# Schema.net
KiCad netlist of a schematic drawn in Altium Designer
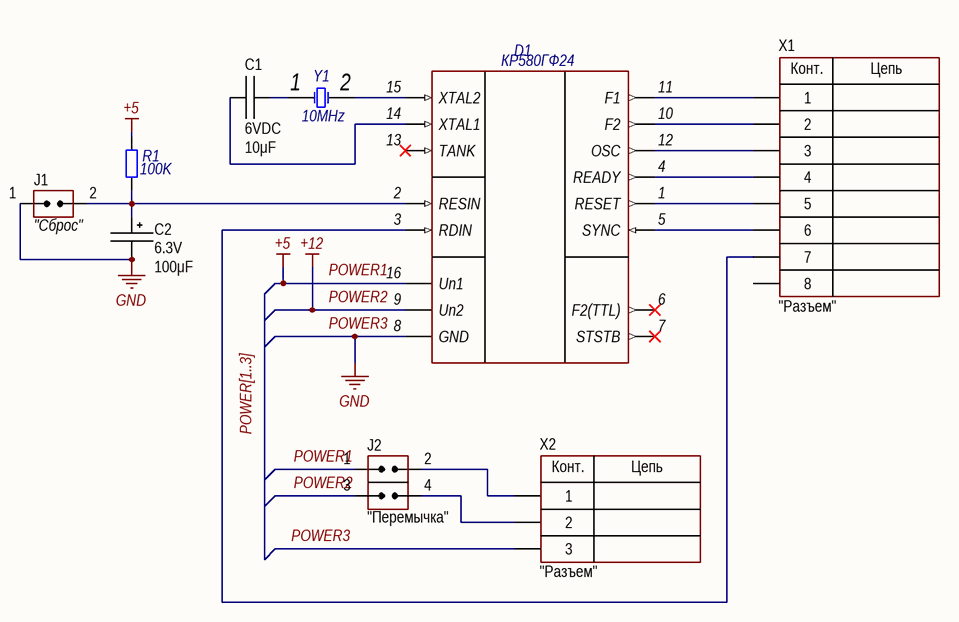
[diagram p0: Schema.SchDoc]

(export (version "E")
  (design (tool "Eeschema 10.0.6"))
  (components
    (comp (ref "C1")
      (value "10μF")
      (footprint "CustomCase:CAP: VY2")
      (fields
        (field (name "MANUFACTURER") "Epcos")
        (field (name "PARTNUMBER") "B32774D4106K000")
        (field (name "VALUEMANUFACTURERPARTNUMBER") "Film capacitor, 10μF, 6VDC, ±10%, 10.9mOhm, 31.5x15 mm, -40...+105°C")
        (field (name "VOLTAGE") "6VDC")
      )
      (libsource (lib "Capacitor") (part "Film"))
    )
    (comp (ref "C2")
      (value "100μF")
      (footprint "StandardCase:CAP: TANTAL-A")
      (fields
        (field (name "MANUFACTURER") "AVX")
        (field (name "PARTNUMBER") "F930J107KAAAJ6")
        (field (name "VALUEMANUFACTURERPARTNUMBER") "Tantalum capacitor, 100μF, 6.3V, ±10%, 2Ohm, case A (3216), -55...+125°C")
        (field (name "VOLTAGE") "6.3V")
      )
      (libsource (lib "Capacitor") (part "Tantal_A"))
    )
    (comp (ref "D1")
      (value "КР580ГФ24")
      (footprint "DIP16")
      (description "Генератор тактовых сигналов")
      (libsource (lib "IC.USSA") (part "КР580ГФ24"))
    )
    (comp (ref "J1")
      (value "~")
      (footprint "CustomCase:CON: PLS-2")
      (fields (field (name "COMMENTTEXT") "\"Сброс\""))
      (libsource (lib "Connector") (part "Jumper_single"))
    )
    (comp (ref "J2")
      (value "~")
      (footprint "CustomCase:CON: PLD-4")
      (fields (field (name "COMMENTTEXT") "\"Перемычка\""))
      (libsource (lib "Connector") (part "Jumper_double"))
    )
    (comp (ref "R1")
      (value "100K")
      (footprint "AXIAL-0.4")
      (description "Resistor")
      (fields (field (name "Comment") "Res2") (field (name "PUBLISHER") "Altium Limited"))
      (libsource (lib "Miscellaneous Devices") (part "Res2"))
    )
    (comp (ref "X1")
      (value "~")
      (footprint "CustomCase:CON: PLD-8")
      (fields
        (field (name "MANUFACTURER") "Connfly")
        (field (name "VALUEMANUFACTURERPARTNUMBER") "Connector, 8pin, 2.54mm, 500VAC, 3A")
        (field (name "PARTNUMBER") "PLD-8")
        (field (name "COMMENTTEXT") "\"Разъем\"")
      )
      (libsource (lib "Connector") (part "PLD-8"))
    )
    (comp (ref "X2")
      (value "~")
      (footprint "CustomCase:CON: PLS-3")
      (fields
        (field (name "MANUFACTURER") "Connfly")
        (field (name "VALUEMANUFACTURERPARTNUMBER") "Connector, 3pin, 2.54mm, 500VAC, 3A")
        (field (name "PARTNUMBER") "PLS-3")
        (field (name "COMMENTTEXT") "\"Разъем\"")
      )
      (libsource (lib "Connector") (part "PLS-3"))
    )
    (comp (ref "Y1")
      (value "10MHz")
      (footprint "R38")
      (description "Crystal Oscillator")
      (fields (field (name "PUBLISHER") "Altium Limited"))
      (libsource (lib "Miscellaneous Devices") (part "XTAL"))
    )
  )
  (nets
    (net (code "1") (name "+5") (class "Default")
      (node (ref "D1") (pin "16") (pinfunction "Uп1_16") (pintype "power_in"))
      (node (ref "R1") (pin "2") (pinfunction "2_2") (pintype "passive"))
    )
    (net (code "2") (name "+12") (class "Default")
      (node (ref "D1") (pin "9") (pinfunction "Uп2_9") (pintype "power_in"))
    )
    (net (code "7") (name "GND") (class "Default")
      (node (ref "C2") (pin "2") (pinfunction "2_2") (pintype "power_in"))
      (node (ref "D1") (pin "8") (pinfunction "GND_8") (pintype "passive"))
      (node (ref "J1") (pin "1") (pinfunction "IN_1") (pintype "passive"))
    )
    (net (code "8") (name "Net-(D1-F1)") (class "Default")
      (node (ref "D1") (pin "11") (pinfunction "F1_11") (pintype "output"))
      (node (ref "X1") (pin "1") (pinfunction "1_1") (pintype "passive"))
    )
    (net (code "9") (name "Net-(D1-F2)") (class "Default")
      (node (ref "D1") (pin "10") (pinfunction "F2_10") (pintype "output"))
      (node (ref "X1") (pin "2") (pinfunction "2_2") (pintype "passive"))
    )
    (net (code "10") (name "Net-(D1-OSC)") (class "Default")
      (node (ref "D1") (pin "12") (pinfunction "OSC_12") (pintype "output"))
      (node (ref "X1") (pin "3") (pinfunction "3_3") (pintype "power_in"))
    )
    (net (code "11") (name "Net-(D1-RDIN)") (class "Default")
      (node (ref "D1") (pin "3") (pinfunction "RDIN_3") (pintype "input"))
      (node (ref "X1") (pin "7") (pinfunction "7_7") (pintype "power_in"))
    )
    (net (code "12") (name "Net-(D1-READY)") (class "Default")
      (node (ref "D1") (pin "4") (pinfunction "READY_4") (pintype "output"))
      (node (ref "X1") (pin "4") (pinfunction "4_4") (pintype "power_in"))
    )
    (net (code "13") (name "Net-(D1-RESET)") (class "Default")
      (node (ref "D1") (pin "1") (pinfunction "RESET_1") (pintype "output"))
      (node (ref "X1") (pin "5") (pinfunction "5_5") (pintype "power_in"))
    )
    (net (code "14") (name "Net-(D1-RESIN)") (class "Default")
      (node (ref "C2") (pin "1") (pinfunction "1_1") (pintype "power_in"))
      (node (ref "D1") (pin "2") (pinfunction "RESIN_2") (pintype "input"))
      (node (ref "J1") (pin "2") (pinfunction "IN_2") (pintype "passive"))
      (node (ref "R1") (pin "1") (pinfunction "1_1") (pintype "passive"))
    )
    (net (code "15") (name "Net-(D1-SYNC)") (class "Default")
      (node (ref "D1") (pin "5") (pinfunction "SYNC_5") (pintype "input"))
      (node (ref "X1") (pin "6") (pinfunction "6_6") (pintype "power_in"))
    )
    (net (code "16") (name "Net-(D1-XTAL1)") (class "Default")
      (node (ref "C1") (pin "2") (pinfunction "2_2") (pintype "power_in"))
      (node (ref "D1") (pin "14") (pinfunction "XTAL1_14") (pintype "input"))
    )
    (net (code "17") (name "Net-(D1-XTAL2)") (class "Default")
      (node (ref "D1") (pin "15") (pinfunction "XTAL2_15") (pintype "input"))
      (node (ref "Y1") (pin "2") (pinfunction "OSC2_2") (pintype "passive"))
    )
    (net (code "18") (name "Net-(J2-IN-Pad2)") (class "Default")
      (node (ref "J2") (pin "2") (pinfunction "IN_2") (pintype "passive"))
      (node (ref "X2") (pin "1") (pinfunction "1_1") (pintype "passive"))
    )
    (net (code "19") (name "Net-(J2-IN-Pad4)") (class "Default")
      (node (ref "J2") (pin "4") (pinfunction "IN_4") (pintype "passive"))
      (node (ref "X2") (pin "2") (pinfunction "2_2") (pintype "passive"))
    )
    (net (code "20") (name "Net-(Y1-OSC1)") (class "Default")
      (node (ref "C1") (pin "1") (pinfunction "1_1") (pintype "power_in"))
      (node (ref "Y1") (pin "1") (pinfunction "OSC1_1") (pintype "passive"))
    )
    (net (code "21") (name "unconnected-(D1-F2(TTL)-Pad6)") (class "Default")
      (node (ref "D1") (pin "6") (pinfunction "F2(TTL)_6") (pintype "output+no_connect"))
    )
    (net (code "22") (name "unconnected-(D1-STSTB-Pad7)") (class "Default")
      (node (ref "D1") (pin "7") (pinfunction "STSTB_7") (pintype "output+no_connect"))
    )
    (net (code "23") (name "unconnected-(D1-TANK-Pad13)") (class "Default")
      (node (ref "D1") (pin "13") (pinfunction "TANK_13") (pintype "input+no_connect"))
    )
    (net (code "24") (name "unconnected-(J2-IN-Pad1)") (class "Default")
      (node (ref "J2") (pin "1") (pinfunction "IN_1") (pintype "passive"))
    )
    (net (code "25") (name "unconnected-(J2-IN-Pad3)") (class "Default")
      (node (ref "J2") (pin "3") (pinfunction "IN_3") (pintype "passive"))
    )
    (net (code "26") (name "unconnected-(X1-Pad8)") (class "Default")
      (node (ref "X1") (pin "8") (pinfunction "8_8") (pintype "power_in"))
    )
    (net (code "27") (name "unconnected-(X2-Pad3)") (class "Default")
      (node (ref "X2") (pin "3") (pinfunction "3_3") (pintype "power_in"))
    )
  )
)
